# RC_Engine_Sound_ESP32.net
KiCad netlist of a schematic drawn in EAGLE
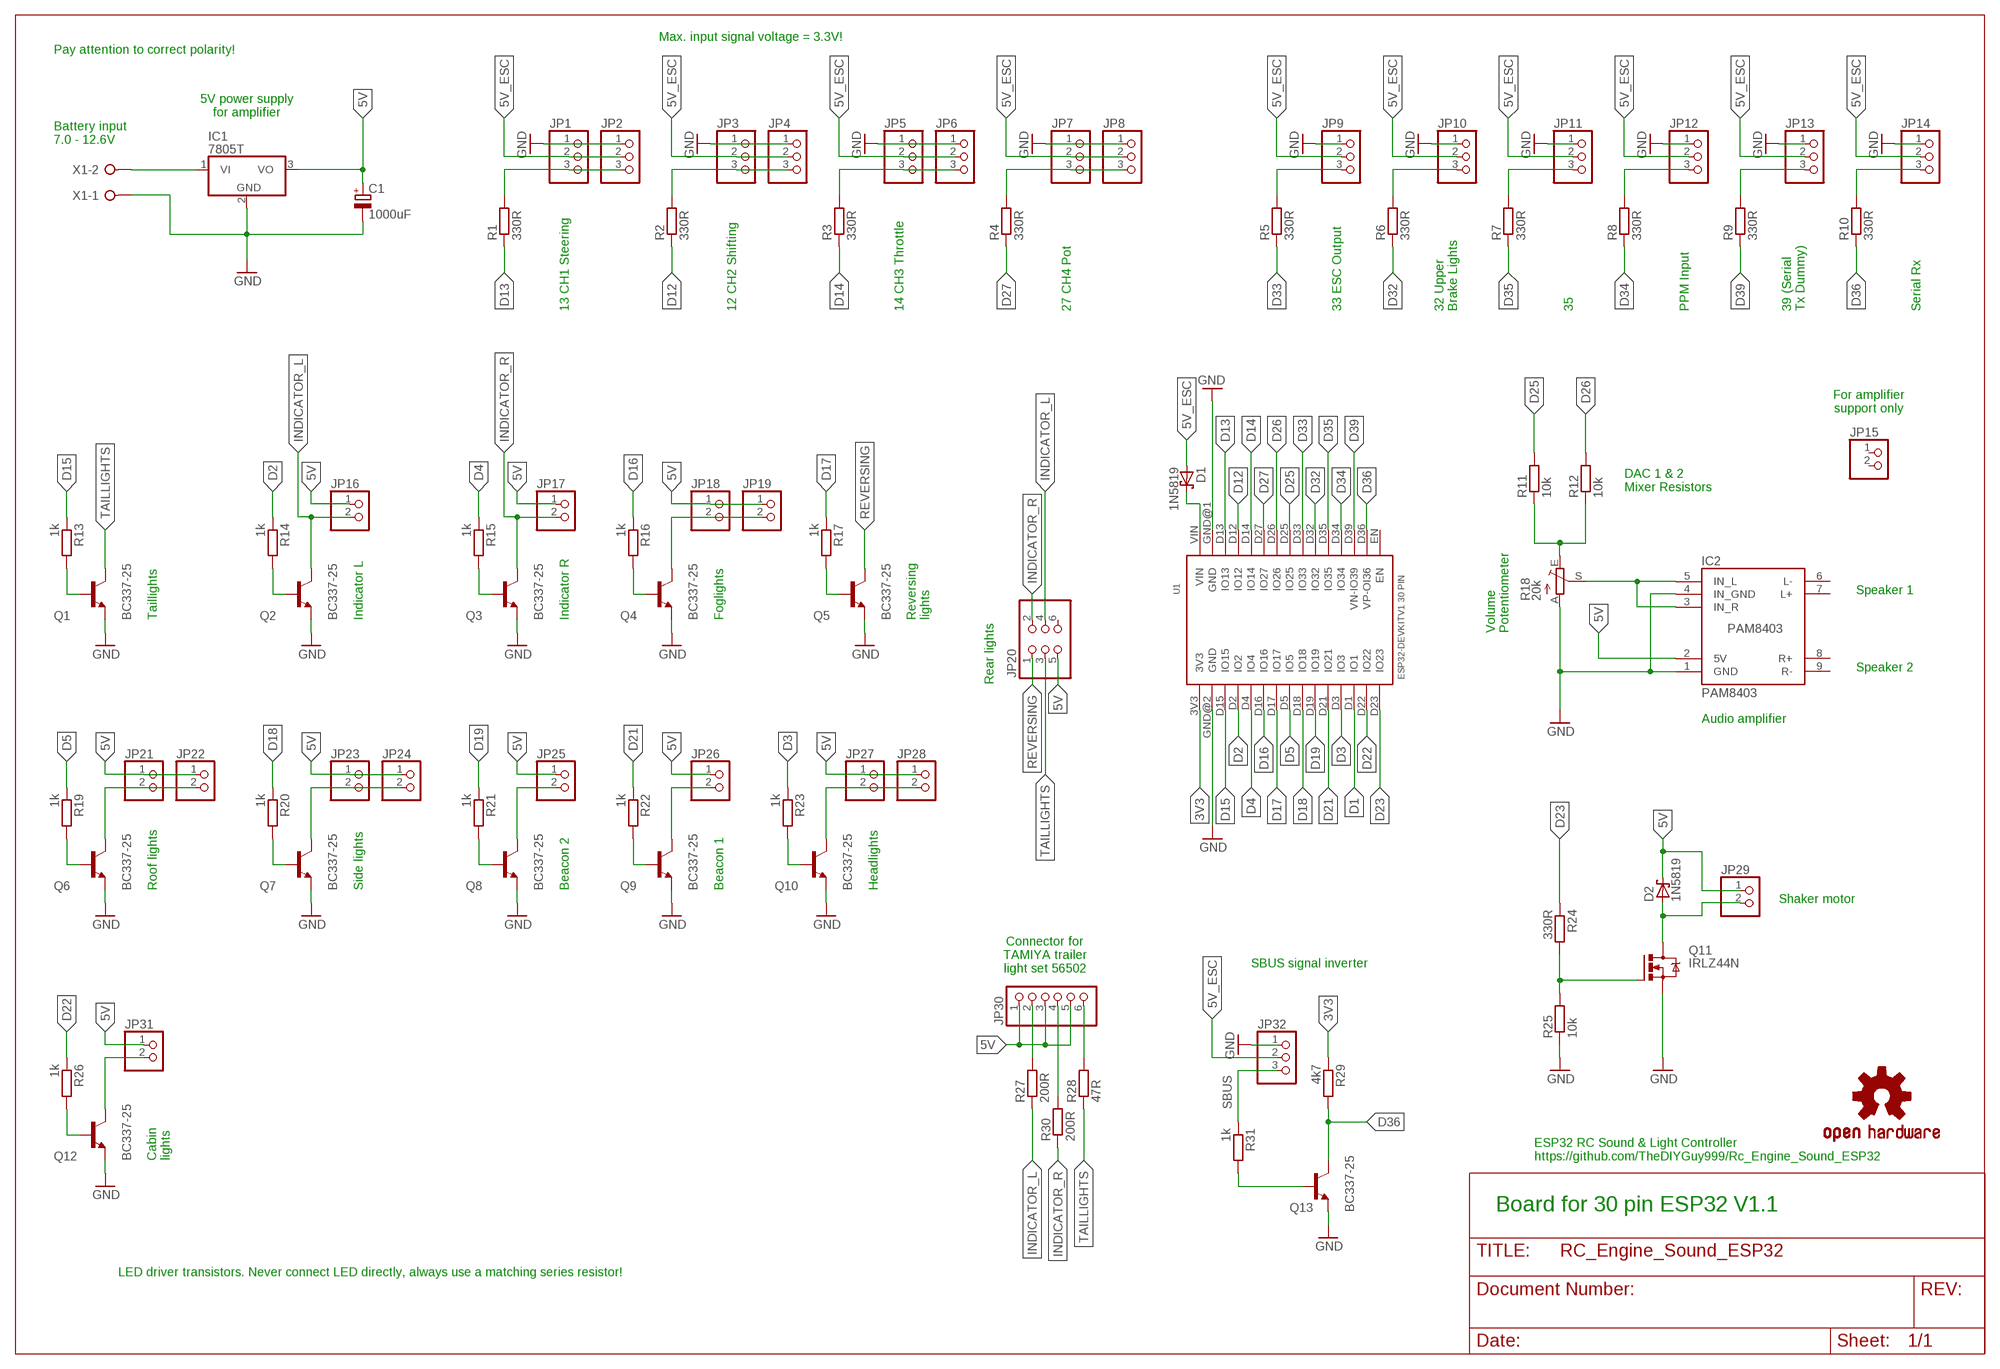
[diagram p0: schematic, sheet 1]

(export (version "E")
  (design (tool "Eeschema 10.0.6"))
  (components
    (comp (ref "C1")
      (value "1000uF")
      (footprint "eagle-import:E5-10,5")
      (libsource (lib "eagle-import") (part "CPOL-EUE5-10.5"))
    )
    (comp (ref "D1")
      (value "1N5819")
      (footprint "eagle-import:DO35-7")
      (libsource (lib "eagle-import") (part "SCHOTTKY-DIODEDO35-7"))
    )
    (comp (ref "D2")
      (value "1N5819")
      (footprint "eagle-import:DO35-7")
      (libsource (lib "eagle-import") (part "SCHOTTKY-DIODEDO35-7"))
    )
    (comp (ref "IC1")
      (value "7805T")
      (footprint "eagle-import:TO220H")
      (libsource (lib "eagle-import") (part "78T05"))
    )
    (comp (ref "IC2")
      (value "PAM8403")
      (footprint "eagle-import:PAM8403")
      (libsource (lib "eagle-import") (part "PAM8403"))
    )
    (comp (ref "JP1")
      (value "PINHD-1X3")
      (footprint "eagle-import:1X03")
      (libsource (lib "eagle-import") (part "PINHD-1X3"))
    )
    (comp (ref "JP2")
      (value "PINHD-1X3")
      (footprint "eagle-import:1X03")
      (libsource (lib "eagle-import") (part "PINHD-1X3"))
    )
    (comp (ref "JP3")
      (value "PINHD-1X3")
      (footprint "eagle-import:1X03")
      (libsource (lib "eagle-import") (part "PINHD-1X3"))
    )
    (comp (ref "JP4")
      (value "PINHD-1X3")
      (footprint "eagle-import:1X03")
      (libsource (lib "eagle-import") (part "PINHD-1X3"))
    )
    (comp (ref "JP5")
      (value "PINHD-1X3")
      (footprint "eagle-import:1X03")
      (libsource (lib "eagle-import") (part "PINHD-1X3"))
    )
    (comp (ref "JP6")
      (value "PINHD-1X3")
      (footprint "eagle-import:1X03")
      (libsource (lib "eagle-import") (part "PINHD-1X3"))
    )
    (comp (ref "JP7")
      (value "PINHD-1X3")
      (footprint "eagle-import:1X03")
      (libsource (lib "eagle-import") (part "PINHD-1X3"))
    )
    (comp (ref "JP8")
      (value "PINHD-1X3")
      (footprint "eagle-import:1X03")
      (libsource (lib "eagle-import") (part "PINHD-1X3"))
    )
    (comp (ref "JP9")
      (value "PINHD-1X3")
      (footprint "eagle-import:1X03")
      (libsource (lib "eagle-import") (part "PINHD-1X3"))
    )
    (comp (ref "JP10")
      (value "PINHD-1X3")
      (footprint "eagle-import:1X03")
      (libsource (lib "eagle-import") (part "PINHD-1X3"))
    )
    (comp (ref "JP11")
      (value "PINHD-1X3")
      (footprint "eagle-import:1X03")
      (libsource (lib "eagle-import") (part "PINHD-1X3"))
    )
    (comp (ref "JP12")
      (value "PINHD-1X3")
      (footprint "eagle-import:1X03")
      (libsource (lib "eagle-import") (part "PINHD-1X3"))
    )
    (comp (ref "JP13")
      (value "PINHD-1X3")
      (footprint "eagle-import:1X03")
      (libsource (lib "eagle-import") (part "PINHD-1X3"))
    )
    (comp (ref "JP14")
      (value "PINHD-1X3")
      (footprint "eagle-import:1X03")
      (libsource (lib "eagle-import") (part "PINHD-1X3"))
    )
    (comp (ref "JP15")
      (value "PINHD-1X2")
      (footprint "eagle-import:1X02")
      (libsource (lib "eagle-import") (part "PINHD-1X2"))
    )
    (comp (ref "JP16")
      (value "PINHD-1X2")
      (footprint "eagle-import:1X02")
      (libsource (lib "eagle-import") (part "PINHD-1X2"))
    )
    (comp (ref "JP17")
      (value "PINHD-1X2")
      (footprint "eagle-import:1X02")
      (libsource (lib "eagle-import") (part "PINHD-1X2"))
    )
    (comp (ref "JP18")
      (value "PINHD-1X2")
      (footprint "eagle-import:1X02")
      (libsource (lib "eagle-import") (part "PINHD-1X2"))
    )
    (comp (ref "JP19")
      (value "PINHD-1X2")
      (footprint "eagle-import:1X02")
      (libsource (lib "eagle-import") (part "PINHD-1X2"))
    )
    (comp (ref "JP20")
      (value "PINHD-2X3")
      (footprint "eagle-import:2X03")
      (libsource (lib "eagle-import") (part "PINHD-2X3"))
    )
    (comp (ref "JP21")
      (value "PINHD-1X2")
      (footprint "eagle-import:1X02")
      (libsource (lib "eagle-import") (part "PINHD-1X2"))
    )
    (comp (ref "JP22")
      (value "PINHD-1X2")
      (footprint "eagle-import:1X02")
      (libsource (lib "eagle-import") (part "PINHD-1X2"))
    )
    (comp (ref "JP23")
      (value "PINHD-1X2")
      (footprint "eagle-import:1X02")
      (libsource (lib "eagle-import") (part "PINHD-1X2"))
    )
    (comp (ref "JP24")
      (value "PINHD-1X2")
      (footprint "eagle-import:1X02")
      (libsource (lib "eagle-import") (part "PINHD-1X2"))
    )
    (comp (ref "JP25")
      (value "PINHD-1X2")
      (footprint "eagle-import:1X02")
      (libsource (lib "eagle-import") (part "PINHD-1X2"))
    )
    (comp (ref "JP26")
      (value "PINHD-1X2")
      (footprint "eagle-import:1X02")
      (libsource (lib "eagle-import") (part "PINHD-1X2"))
    )
    (comp (ref "JP27")
      (value "PINHD-1X2")
      (footprint "eagle-import:1X02")
      (libsource (lib "eagle-import") (part "PINHD-1X2"))
    )
    (comp (ref "JP28")
      (value "PINHD-1X2")
      (footprint "eagle-import:1X02")
      (libsource (lib "eagle-import") (part "PINHD-1X2"))
    )
    (comp (ref "JP29")
      (value "PINHD-1X2")
      (footprint "eagle-import:1X02")
      (libsource (lib "eagle-import") (part "PINHD-1X2"))
    )
    (comp (ref "JP30")
      (value "PINHD-1X6")
      (footprint "eagle-import:1X06")
      (libsource (lib "eagle-import") (part "PINHD-1X6"))
    )
    (comp (ref "JP31")
      (value "PINHD-1X2")
      (footprint "eagle-import:1X02")
      (libsource (lib "eagle-import") (part "PINHD-1X2"))
    )
    (comp (ref "JP32")
      (value "PINHD-1X3")
      (footprint "eagle-import:1X03")
      (libsource (lib "eagle-import") (part "PINHD-1X3"))
    )
    (comp (ref "LOGO1")
      (value "OSHW-LOGOM")
      (footprint "eagle-import:OSHW-LOGO-M")
      (libsource (lib "eagle-import") (part "OSHW-LOGOM"))
    )
    (comp (ref "Q1")
      (value "BC337-25")
      (footprint "eagle-import:TO92")
      (libsource (lib "eagle-import") (part "BC337-25"))
    )
    (comp (ref "Q2")
      (value "BC337-25")
      (footprint "eagle-import:TO92")
      (libsource (lib "eagle-import") (part "BC337-25"))
    )
    (comp (ref "Q3")
      (value "BC337-25")
      (footprint "eagle-import:TO92")
      (libsource (lib "eagle-import") (part "BC337-25"))
    )
    (comp (ref "Q4")
      (value "BC337-25")
      (footprint "eagle-import:TO92")
      (libsource (lib "eagle-import") (part "BC337-25"))
    )
    (comp (ref "Q5")
      (value "BC337-25")
      (footprint "eagle-import:TO92")
      (libsource (lib "eagle-import") (part "BC337-25"))
    )
    (comp (ref "Q6")
      (value "BC337-25")
      (footprint "eagle-import:TO92")
      (libsource (lib "eagle-import") (part "BC337-25"))
    )
    (comp (ref "Q7")
      (value "BC337-25")
      (footprint "eagle-import:TO92")
      (libsource (lib "eagle-import") (part "BC337-25"))
    )
    (comp (ref "Q8")
      (value "BC337-25")
      (footprint "eagle-import:TO92")
      (libsource (lib "eagle-import") (part "BC337-25"))
    )
    (comp (ref "Q9")
      (value "BC337-25")
      (footprint "eagle-import:TO92")
      (libsource (lib "eagle-import") (part "BC337-25"))
    )
    (comp (ref "Q10")
      (value "BC337-25")
      (footprint "eagle-import:TO92")
      (libsource (lib "eagle-import") (part "BC337-25"))
    )
    (comp (ref "Q11")
      (value "IRLZ44N")
      (footprint "eagle-import:TO220BV")
      (libsource (lib "eagle-import") (part "IRF540"))
    )
    (comp (ref "Q12")
      (value "BC337-25")
      (footprint "eagle-import:TO92")
      (libsource (lib "eagle-import") (part "BC337-25"))
    )
    (comp (ref "Q13")
      (value "BC337-25")
      (footprint "eagle-import:TO92")
      (libsource (lib "eagle-import") (part "BC337-25"))
    )
    (comp (ref "R1")
      (value "330R")
      (footprint "eagle-import:0207_2V")
      (libsource (lib "eagle-import") (part "R-EU_0207/2V"))
    )
    (comp (ref "R2")
      (value "330R")
      (footprint "eagle-import:0207_2V")
      (libsource (lib "eagle-import") (part "R-EU_0207/2V"))
    )
    (comp (ref "R3")
      (value "330R")
      (footprint "eagle-import:0207_2V")
      (libsource (lib "eagle-import") (part "R-EU_0207/2V"))
    )
    (comp (ref "R4")
      (value "330R")
      (footprint "eagle-import:0207_2V")
      (libsource (lib "eagle-import") (part "R-EU_0207/2V"))
    )
    (comp (ref "R5")
      (value "330R")
      (footprint "eagle-import:0207_2V")
      (libsource (lib "eagle-import") (part "R-EU_0207/2V"))
    )
    (comp (ref "R6")
      (value "330R")
      (footprint "eagle-import:0207_2V")
      (libsource (lib "eagle-import") (part "R-EU_0207/2V"))
    )
    (comp (ref "R7")
      (value "330R")
      (footprint "eagle-import:0207_2V")
      (libsource (lib "eagle-import") (part "R-EU_0207/2V"))
    )
    (comp (ref "R8")
      (value "330R")
      (footprint "eagle-import:0207_2V")
      (libsource (lib "eagle-import") (part "R-EU_0207/2V"))
    )
    (comp (ref "R9")
      (value "330R")
      (footprint "eagle-import:0207_2V")
      (libsource (lib "eagle-import") (part "R-EU_0207/2V"))
    )
    (comp (ref "R10")
      (value "330R")
      (footprint "eagle-import:0207_2V")
      (libsource (lib "eagle-import") (part "R-EU_0207/2V"))
    )
    (comp (ref "R11")
      (value "10k")
      (footprint "eagle-import:0207_10")
      (libsource (lib "eagle-import") (part "R-EU_0207/10"))
    )
    (comp (ref "R12")
      (value "10k")
      (footprint "eagle-import:0207_10")
      (libsource (lib "eagle-import") (part "R-EU_0207/10"))
    )
    (comp (ref "R13")
      (value "1k")
      (footprint "eagle-import:0207_2V")
      (libsource (lib "eagle-import") (part "R-EU_0207/2V"))
    )
    (comp (ref "R14")
      (value "1k")
      (footprint "eagle-import:0207_2V")
      (libsource (lib "eagle-import") (part "R-EU_0207/2V"))
    )
    (comp (ref "R15")
      (value "1k")
      (footprint "eagle-import:0207_2V")
      (libsource (lib "eagle-import") (part "R-EU_0207/2V"))
    )
    (comp (ref "R16")
      (value "1k")
      (footprint "eagle-import:0207_2V")
      (libsource (lib "eagle-import") (part "R-EU_0207/2V"))
    )
    (comp (ref "R17")
      (value "1k")
      (footprint "eagle-import:0207_2V")
      (libsource (lib "eagle-import") (part "R-EU_0207/2V"))
    )
    (comp (ref "R18")
      (value "20k")
      (footprint "eagle-import:S64W")
      (libsource (lib "eagle-import") (part "TRIM_EU-S64W"))
    )
    (comp (ref "R19")
      (value "1k")
      (footprint "eagle-import:0207_2V")
      (libsource (lib "eagle-import") (part "R-EU_0207/2V"))
    )
    (comp (ref "R20")
      (value "1k")
      (footprint "eagle-import:0207_2V")
      (libsource (lib "eagle-import") (part "R-EU_0207/2V"))
    )
    (comp (ref "R21")
      (value "1k")
      (footprint "eagle-import:0207_2V")
      (libsource (lib "eagle-import") (part "R-EU_0207/2V"))
    )
    (comp (ref "R22")
      (value "1k")
      (footprint "eagle-import:0207_2V")
      (libsource (lib "eagle-import") (part "R-EU_0207/2V"))
    )
    (comp (ref "R23")
      (value "1k")
      (footprint "eagle-import:0207_2V")
      (libsource (lib "eagle-import") (part "R-EU_0207/2V"))
    )
    (comp (ref "R24")
      (value "330R")
      (footprint "eagle-import:0207_2V")
      (libsource (lib "eagle-import") (part "R-EU_0207/2V"))
    )
    (comp (ref "R25")
      (value "10k")
      (footprint "eagle-import:0207_2V")
      (libsource (lib "eagle-import") (part "R-EU_0207/2V"))
    )
    (comp (ref "R26")
      (value "1k")
      (footprint "eagle-import:0207_2V")
      (libsource (lib "eagle-import") (part "R-EU_0207/2V"))
    )
    (comp (ref "R27")
      (value "200R")
      (footprint "eagle-import:0207_10")
      (libsource (lib "eagle-import") (part "R-EU_0207/10"))
    )
    (comp (ref "R28")
      (value "47R")
      (footprint "eagle-import:0207_10")
      (libsource (lib "eagle-import") (part "R-EU_0207/10"))
    )
    (comp (ref "R29")
      (value "4k7")
      (footprint "eagle-import:0207_2V")
      (libsource (lib "eagle-import") (part "R-EU_0207/2V"))
    )
    (comp (ref "R30")
      (value "200R")
      (footprint "eagle-import:0207_10")
      (libsource (lib "eagle-import") (part "R-EU_0207/10"))
    )
    (comp (ref "R31")
      (value "1k")
      (footprint "eagle-import:0207_2V")
      (libsource (lib "eagle-import") (part "R-EU_0207/2V"))
    )
    (comp (ref "U1")
      (value "ESP32DEVKITV1")
      (footprint "eagle-import:ESP32-DEVKITV1")
      (libsource (lib "eagle-import") (part "ESP32DEVKITV1"))
    )
    (comp (ref "X1")
      (value "W237-02P")
      (footprint "eagle-import:W237-132")
      (libsource (lib "eagle-import") (part "W237-02P"))
    )
  )
  (nets
    (net (code "1") (name "/SBUS") (class "Default")
      (node (ref "JP32") (pin "3") (pinfunction "3_3") (pintype "passive"))
      (node (ref "R31") (pin "1") (pinfunction "1_1") (pintype "passive"))
    )
    (net (code "2") (name "3V3") (class "Default")
      (node (ref "R29") (pin "1") (pinfunction "1_1") (pintype "passive"))
      (node (ref "U1") (pin "3V3") (pinfunction "3V3_3V3") (pintype "bidirectional"))
    )
    (net (code "3") (name "5V") (class "Default")
      (node (ref "C1") (pin "+") (pinfunction "+_+") (pintype "passive"))
      (node (ref "D2") (pin "C") (pinfunction "C_C") (pintype "passive"))
      (node (ref "IC1") (pin "3") (pinfunction "VO_3") (pintype "passive"))
      (node (ref "IC2") (pin "2") (pinfunction "5V_2") (pintype "input"))
      (node (ref "JP16") (pin "1") (pinfunction "1_1") (pintype "passive"))
      (node (ref "JP17") (pin "1") (pinfunction "1_1") (pintype "passive"))
      (node (ref "JP18") (pin "1") (pinfunction "1_1") (pintype "passive"))
      (node (ref "JP19") (pin "1") (pinfunction "1_1") (pintype "passive"))
      (node (ref "JP20") (pin "5") (pinfunction "5_5") (pintype "passive"))
      (node (ref "JP21") (pin "1") (pinfunction "1_1") (pintype "passive"))
      (node (ref "JP22") (pin "1") (pinfunction "1_1") (pintype "passive"))
      (node (ref "JP23") (pin "1") (pinfunction "1_1") (pintype "passive"))
      (node (ref "JP24") (pin "1") (pinfunction "1_1") (pintype "passive"))
      (node (ref "JP25") (pin "1") (pinfunction "1_1") (pintype "passive"))
      (node (ref "JP26") (pin "1") (pinfunction "1_1") (pintype "passive"))
      (node (ref "JP27") (pin "1") (pinfunction "1_1") (pintype "passive"))
      (node (ref "JP28") (pin "1") (pinfunction "1_1") (pintype "passive"))
      (node (ref "JP29") (pin "1") (pinfunction "1_1") (pintype "passive"))
      (node (ref "JP30") (pin "1") (pinfunction "1_1") (pintype "passive"))
      (node (ref "JP30") (pin "3") (pinfunction "3_3") (pintype "passive"))
      (node (ref "JP30") (pin "5") (pinfunction "5_5") (pintype "passive"))
      (node (ref "JP31") (pin "1") (pinfunction "1_1") (pintype "passive"))
    )
    (net (code "4") (name "5V_ESC") (class "Default")
      (node (ref "D1") (pin "A") (pinfunction "A_A") (pintype "passive"))
      (node (ref "JP1") (pin "2") (pinfunction "2_2") (pintype "passive"))
      (node (ref "JP10") (pin "2") (pinfunction "2_2") (pintype "passive"))
      (node (ref "JP11") (pin "2") (pinfunction "2_2") (pintype "passive"))
      (node (ref "JP12") (pin "2") (pinfunction "2_2") (pintype "passive"))
      (node (ref "JP13") (pin "2") (pinfunction "2_2") (pintype "passive"))
      (node (ref "JP14") (pin "2") (pinfunction "2_2") (pintype "passive"))
      (node (ref "JP2") (pin "2") (pinfunction "2_2") (pintype "passive"))
      (node (ref "JP3") (pin "2") (pinfunction "2_2") (pintype "passive"))
      (node (ref "JP32") (pin "2") (pinfunction "2_2") (pintype "passive"))
      (node (ref "JP4") (pin "2") (pinfunction "2_2") (pintype "passive"))
      (node (ref "JP5") (pin "2") (pinfunction "2_2") (pintype "passive"))
      (node (ref "JP6") (pin "2") (pinfunction "2_2") (pintype "passive"))
      (node (ref "JP7") (pin "2") (pinfunction "2_2") (pintype "passive"))
      (node (ref "JP8") (pin "2") (pinfunction "2_2") (pintype "passive"))
      (node (ref "JP9") (pin "2") (pinfunction "2_2") (pintype "passive"))
    )
    (net (code "5") (name "D1") (class "Default")
      (node (ref "U1") (pin "D1") (pinfunction "IO1_D1") (pintype "bidirectional"))
    )
    (net (code "6") (name "D2") (class "Default")
      (node (ref "R14") (pin "1") (pinfunction "1_1") (pintype "passive"))
      (node (ref "U1") (pin "D2") (pinfunction "IO2_D2") (pintype "bidirectional"))
    )
    (net (code "7") (name "D3") (class "Default")
      (node (ref "R23") (pin "1") (pinfunction "1_1") (pintype "passive"))
      (node (ref "U1") (pin "D3") (pinfunction "IO3_D3") (pintype "bidirectional"))
    )
    (net (code "8") (name "D4") (class "Default")
      (node (ref "R15") (pin "1") (pinfunction "1_1") (pintype "passive"))
      (node (ref "U1") (pin "D4") (pinfunction "IO4_D4") (pintype "bidirectional"))
    )
    (net (code "9") (name "D5") (class "Default")
      (node (ref "R19") (pin "1") (pinfunction "1_1") (pintype "passive"))
      (node (ref "U1") (pin "D5") (pinfunction "IO5_D5") (pintype "bidirectional"))
    )
    (net (code "10") (name "D12") (class "Default")
      (node (ref "R2") (pin "1") (pinfunction "1_1") (pintype "passive"))
      (node (ref "U1") (pin "D12") (pinfunction "IO12_D12") (pintype "bidirectional"))
    )
    (net (code "11") (name "D13") (class "Default")
      (node (ref "R1") (pin "1") (pinfunction "1_1") (pintype "passive"))
      (node (ref "U1") (pin "D13") (pinfunction "IO13_D13") (pintype "bidirectional"))
    )
    (net (code "12") (name "D14") (class "Default")
      (node (ref "R3") (pin "1") (pinfunction "1_1") (pintype "passive"))
      (node (ref "U1") (pin "D14") (pinfunction "IO14_D14") (pintype "bidirectional"))
    )
    (net (code "13") (name "D15") (class "Default")
      (node (ref "R13") (pin "1") (pinfunction "1_1") (pintype "passive"))
      (node (ref "U1") (pin "D15") (pinfunction "IO15_D15") (pintype "bidirectional"))
    )
    (net (code "14") (name "D16") (class "Default")
      (node (ref "R16") (pin "1") (pinfunction "1_1") (pintype "passive"))
      (node (ref "U1") (pin "D16") (pinfunction "IO16_D16") (pintype "bidirectional"))
    )
    (net (code "15") (name "D17") (class "Default")
      (node (ref "R17") (pin "1") (pinfunction "1_1") (pintype "passive"))
      (node (ref "U1") (pin "D17") (pinfunction "IO17_D17") (pintype "bidirectional"))
    )
    (net (code "16") (name "D18") (class "Default")
      (node (ref "R20") (pin "1") (pinfunction "1_1") (pintype "passive"))
      (node (ref "U1") (pin "D18") (pinfunction "IO18_D18") (pintype "bidirectional"))
    )
    (net (code "17") (name "D19") (class "Default")
      (node (ref "R21") (pin "1") (pinfunction "1_1") (pintype "passive"))
      (node (ref "U1") (pin "D19") (pinfunction "IO19_D19") (pintype "bidirectional"))
    )
    (net (code "18") (name "D21") (class "Default")
      (node (ref "R22") (pin "1") (pinfunction "1_1") (pintype "passive"))
      (node (ref "U1") (pin "D21") (pinfunction "IO21_D21") (pintype "bidirectional"))
    )
    (net (code "19") (name "D22") (class "Default")
      (node (ref "R26") (pin "1") (pinfunction "1_1") (pintype "passive"))
      (node (ref "U1") (pin "D22") (pinfunction "IO22_D22") (pintype "bidirectional"))
    )
    (net (code "20") (name "D23") (class "Default")
      (node (ref "R24") (pin "1") (pinfunction "1_1") (pintype "passive"))
      (node (ref "U1") (pin "D23") (pinfunction "IO23_D23") (pintype "bidirectional"))
    )
    (net (code "21") (name "D25") (class "Default")
      (node (ref "R11") (pin "2") (pinfunction "2_2") (pintype "passive"))
      (node (ref "U1") (pin "D25") (pinfunction "IO25_D25") (pintype "bidirectional"))
    )
    (net (code "22") (name "D26") (class "Default")
      (node (ref "R12") (pin "2") (pinfunction "2_2") (pintype "passive"))
      (node (ref "U1") (pin "D26") (pinfunction "IO26_D26") (pintype "bidirectional"))
    )
    (net (code "23") (name "D27") (class "Default")
      (node (ref "R4") (pin "1") (pinfunction "1_1") (pintype "passive"))
      (node (ref "U1") (pin "D27") (pinfunction "IO27_D27") (pintype "bidirectional"))
    )
    (net (code "24") (name "D32") (class "Default")
      (node (ref "R6") (pin "1") (pinfunction "1_1") (pintype "passive"))
      (node (ref "U1") (pin "D32") (pinfunction "IO32_D32") (pintype "bidirectional"))
    )
    (net (code "25") (name "D33") (class "Default")
      (node (ref "R5") (pin "1") (pinfunction "1_1") (pintype "passive"))
      (node (ref "U1") (pin "D33") (pinfunction "IO33_D33") (pintype "bidirectional"))
    )
    (net (code "26") (name "D34") (class "Default")
      (node (ref "R8") (pin "1") (pinfunction "1_1") (pintype "passive"))
      (node (ref "U1") (pin "D34") (pinfunction "IO34_D34") (pintype "bidirectional"))
    )
    (net (code "27") (name "D35") (class "Default")
      (node (ref "R7") (pin "1") (pinfunction "1_1") (pintype "passive"))
      (node (ref "U1") (pin "D35") (pinfunction "IO35_D35") (pintype "bidirectional"))
    )
    (net (code "28") (name "D36") (class "Default")
      (node (ref "Q13") (pin "3") (pinfunction "C_3") (pintype "passive"))
      (node (ref "R10") (pin "1") (pinfunction "1_1") (pintype "passive"))
      (node (ref "R29") (pin "2") (pinfunction "2_2") (pintype "passive"))
      (node (ref "U1") (pin "D36") (pinfunction "VP-OI36_D36") (pintype "bidirectional"))
    )
    (net (code "29") (name "D39") (class "Default")
      (node (ref "R9") (pin "1") (pinfunction "1_1") (pintype "passive"))
      (node (ref "U1") (pin "D39") (pinfunction "VN-IO39_D39") (pintype "bidirectional"))
    )
    (net (code "30") (name "GND") (class "Default")
      (node (ref "C1") (pin "-") (pinfunction "-_-") (pintype "passive"))
      (node (ref "IC1") (pin "2") (pinfunction "GND_2") (pintype "passive"))
      (node (ref "IC2") (pin "1") (pinfunction "GND_1") (pintype "input"))
      (node (ref "IC2") (pin "4") (pinfunction "IN_GND_4") (pintype "input"))
      (node (ref "JP1") (pin "1") (pinfunction "1_1") (pintype "passive"))
      (node (ref "JP10") (pin "1") (pinfunction "1_1") (pintype "passive"))
      (node (ref "JP11") (pin "1") (pinfunction "1_1") (pintype "passive"))
      (node (ref "JP12") (pin "1") (pinfunction "1_1") (pintype "passive"))
      (node (ref "JP13") (pin "1") (pinfunction "1_1") (pintype "passive"))
      (node (ref "JP14") (pin "1") (pinfunction "1_1") (pintype "passive"))
      (node (ref "JP2") (pin "1") (pinfunction "1_1") (pintype "passive"))
      (node (ref "JP3") (pin "1") (pinfunction "1_1") (pintype "passive"))
      (node (ref "JP32") (pin "1") (pinfunction "1_1") (pintype "passive"))
      (node (ref "JP4") (pin "1") (pinfunction "1_1") (pintype "passive"))
      (node (ref "JP5") (pin "1") (pinfunction "1_1") (pintype "passive"))
      (node (ref "JP6") (pin "1") (pinfunction "1_1") (pintype "passive"))
      (node (ref "JP7") (pin "1") (pinfunction "1_1") (pintype "passive"))
      (node (ref "JP8") (pin "1") (pinfunction "1_1") (pintype "passive"))
      (node (ref "JP9") (pin "1") (pinfunction "1_1") (pintype "passive"))
      (node (ref "Q1") (pin "1") (pinfunction "E_1") (pintype "passive"))
      (node (ref "Q10") (pin "1") (pinfunction "E_1") (pintype "passive"))
      (node (ref "Q11") (pin "S") (pinfunction "S_S") (pintype "passive"))
      (node (ref "Q12") (pin "1") (pinfunction "E_1") (pintype "passive"))
      (node (ref "Q13") (pin "1") (pinfunction "E_1") (pintype "passive"))
      (node (ref "Q2") (pin "1") (pinfunction "E_1") (pintype "passive"))
      (node (ref "Q3") (pin "1") (pinfunction "E_1") (pintype "passive"))
      (node (ref "Q4") (pin "1") (pinfunction "E_1") (pintype "passive"))
      (node (ref "Q5") (pin "1") (pinfunction "E_1") (pintype "passive"))
      (node (ref "Q6") (pin "1") (pinfunction "E_1") (pintype "passive"))
      (node (ref "Q7") (pin "1") (pinfunction "E_1") (pintype "passive"))
      (node (ref "Q8") (pin "1") (pinfunction "E_1") (pintype "passive"))
      (node (ref "Q9") (pin "1") (pinfunction "E_1") (pintype "passive"))
      (node (ref "R18") (pin "A") (pinfunction "A_A") (pintype "passive"))
      (node (ref "R25") (pin "1") (pinfunction "1_1") (pintype "passive"))
      (node (ref "U1") (pin "GND@1") (pinfunction "GND_GND@1") (pintype "bidirectional"))
      (node (ref "U1") (pin "GND@2") (pinfunction "GND_GND@2") (pintype "bidirectional"))
      (node (ref "X1") (pin "1") (pinfunction "KL_1") (pintype "passive"))
    )
    (net (code "31") (name "INDICATOR_L") (class "Default")
      (node (ref "JP16") (pin "2") (pinfunction "2_2") (pintype "passive"))
      (node (ref "JP20") (pin "4") (pinfunction "4_4") (pintype "passive"))
      (node (ref "Q2") (pin "3") (pinfunction "C_3") (pintype "passive"))
      (node (ref "R27") (pin "1") (pinfunction "1_1") (pintype "passive"))
    )
    (net (code "32") (name "INDICATOR_R") (class "Default")
      (node (ref "JP17") (pin "2") (pinfunction "2_2") (pintype "passive"))
      (node (ref "JP20") (pin "2") (pinfunction "2_2") (pintype "passive"))
      (node (ref "Q3") (pin "3") (pinfunction "C_3") (pintype "passive"))
      (node (ref "R30") (pin "1") (pinfunction "1_1") (pintype "passive"))
    )
    (net (code "33") (name "Net-(D1-PadC)") (class "Default")
      (node (ref "D1") (pin "C") (pinfunction "C_C") (pintype "passive"))
      (node (ref "U1") (pin "VIN") (pinfunction "VIN_VIN") (pintype "bidirectional"))
    )
    (net (code "34") (name "Net-(D2-PadA)") (class "Default")
      (node (ref "D2") (pin "A") (pinfunction "A_A") (pintype "passive"))
      (node (ref "JP29") (pin "2") (pinfunction "2_2") (pintype "passive"))
      (node (ref "Q11") (pin "D") (pinfunction "D_D") (pintype "passive"))
    )
    (net (code "35") (name "Net-(IC1-VI)") (class "Default")
      (node (ref "IC1") (pin "1") (pinfunction "VI_1") (pintype "input"))
      (node (ref "X1") (pin "2") (pinfunction "KL_2") (pintype "passive"))
    )
    (net (code "36") (name "Net-(IC2-IN_L)") (class "Default")
      (node (ref "IC2") (pin "3") (pinfunction "IN_R_3") (pintype "input"))
      (node (ref "IC2") (pin "5") (pinfunction "IN_L_5") (pintype "input"))
      (node (ref "R18") (pin "S") (pinfunction "S_S") (pintype "passive"))
    )
    (net (code "37") (name "Net-(JP1-Pad3)") (class "Default")
      (node (ref "JP1") (pin "3") (pinfunction "3_3") (pintype "passive"))
      (node (ref "JP2") (pin "3") (pinfunction "3_3") (pintype "passive"))
      (node (ref "R1") (pin "2") (pinfunction "2_2") (pintype "passive"))
    )
    (net (code "38") (name "Net-(JP3-Pad3)") (class "Default")
      (node (ref "JP3") (pin "3") (pinfunction "3_3") (pintype "passive"))
      (node (ref "JP4") (pin "3") (pinfunction "3_3") (pintype "passive"))
      (node (ref "R2") (pin "2") (pinfunction "2_2") (pintype "passive"))
    )
    (net (code "39") (name "Net-(JP5-Pad3)") (class "Default")
      (node (ref "JP5") (pin "3") (pinfunction "3_3") (pintype "passive"))
      (node (ref "JP6") (pin "3") (pinfunction "3_3") (pintype "passive"))
      (node (ref "R3") (pin "2") (pinfunction "2_2") (pintype "passive"))
    )
    (net (code "40") (name "Net-(JP7-Pad3)") (class "Default")
      (node (ref "JP7") (pin "3") (pinfunction "3_3") (pintype "passive"))
      (node (ref "JP8") (pin "3") (pinfunction "3_3") (pintype "passive"))
      (node (ref "R4") (pin "2") (pinfunction "2_2") (pintype "passive"))
    )
    (net (code "41") (name "Net-(JP9-Pad3)") (class "Default")
      (node (ref "JP9") (pin "3") (pinfunction "3_3") (pintype "passive"))
      (node (ref "R5") (pin "2") (pinfunction "2_2") (pintype "passive"))
    )
    (net (code "42") (name "Net-(JP10-Pad3)") (class "Default")
      (node (ref "JP10") (pin "3") (pinfunction "3_3") (pintype "passive"))
      (node (ref "R6") (pin "2") (pinfunction "2_2") (pintype "passive"))
    )
    (net (code "43") (name "Net-(JP11-Pad3)") (class "Default")
      (node (ref "JP11") (pin "3") (pinfunction "3_3") (pintype "passive"))
      (node (ref "R7") (pin "2") (pinfunction "2_2") (pintype "passive"))
    )
    (net (code "44") (name "Net-(JP12-Pad3)") (class "Default")
      (node (ref "JP12") (pin "3") (pinfunction "3_3") (pintype "passive"))
      (node (ref "R8") (pin "2") (pinfunction "2_2") (pintype "passive"))
    )
    (net (code "45") (name "Net-(JP13-Pad3)") (class "Default")
      (node (ref "JP13") (pin "3") (pinfunction "3_3") (pintype "passive"))
      (node (ref "R9") (pin "2") (pinfunction "2_2") (pintype "passive"))
    )
    (net (code "46") (name "Net-(JP14-Pad3)") (class "Default")
      (node (ref "JP14") (pin "3") (pinfunction "3_3") (pintype "passive"))
      (node (ref "R10") (pin "2") (pinfunction "2_2") (pintype "passive"))
    )
    (net (code "47") (name "Net-(JP30-Pad2)") (class "Default")
      (node (ref "JP30") (pin "2") (pinfunction "2_2") (pintype "passive"))
      (node (ref "R27") (pin "2") (pinfunction "2_2") (pintype "passive"))
    )
    (net (code "48") (name "Net-(JP30-Pad4)") (class "Default")
      (node (ref "JP30") (pin "4") (pinfunction "4_4") (pintype "passive"))
      (node (ref "R30") (pin "2") (pinfunction "2_2") (pintype "passive"))
    )
    (net (code "49") (name "Net-(JP30-Pad6)") (class "Default")
      (node (ref "JP30") (pin "6") (pinfunction "6_6") (pintype "passive"))
      (node (ref "R28") (pin "2") (pinfunction "2_2") (pintype "passive"))
    )
    (net (code "50") (name "Net-(Q1-B)") (class "Default")
      (node (ref "Q1") (pin "2") (pinfunction "B_2") (pintype "passive"))
      (node (ref "R13") (pin "2") (pinfunction "2_2") (pintype "passive"))
    )
    (net (code "51") (name "Net-(Q2-B)") (class "Default")
      (node (ref "Q2") (pin "2") (pinfunction "B_2") (pintype "passive"))
      (node (ref "R14") (pin "2") (pinfunction "2_2") (pintype "passive"))
    )
    (net (code "52") (name "Net-(Q3-B)") (class "Default")
      (node (ref "Q3") (pin "2") (pinfunction "B_2") (pintype "passive"))
      (node (ref "R15") (pin "2") (pinfunction "2_2") (pintype "passive"))
    )
    (net (code "53") (name "Net-(Q4-B)") (class "Default")
      (node (ref "Q4") (pin "2") (pinfunction "B_2") (pintype "passive"))
      (node (ref "R16") (pin "2") (pinfunction "2_2") (pintype "passive"))
    )
    (net (code "54") (name "Net-(Q4-C)") (class "Default")
      (node (ref "JP18") (pin "2") (pinfunction "2_2") (pintype "passive"))
      (node (ref "JP19") (pin "2") (pinfunction "2_2") (pintype "passive"))
      (node (ref "Q4") (pin "3") (pinfunction "C_3") (pintype "passive"))
    )
    (net (code "55") (name "Net-(Q5-B)") (class "Default")
      (node (ref "Q5") (pin "2") (pinfunction "B_2") (pintype "passive"))
      (node (ref "R17") (pin "2") (pinfunction "2_2") (pintype "passive"))
    )
    (net (code "56") (name "Net-(Q6-B)") (class "Default")
      (node (ref "Q6") (pin "2") (pinfunction "B_2") (pintype "passive"))
      (node (ref "R19") (pin "2") (pinfunction "2_2") (pintype "passive"))
    )
    (net (code "57") (name "Net-(Q6-C)") (class "Default")
      (node (ref "JP21") (pin "2") (pinfunction "2_2") (pintype "passive"))
      (node (ref "JP22") (pin "2") (pinfunction "2_2") (pintype "passive"))
      (node (ref "Q6") (pin "3") (pinfunction "C_3") (pintype "passive"))
    )
    (net (code "58") (name "Net-(Q7-B)") (class "Default")
      (node (ref "Q7") (pin "2") (pinfunction "B_2") (pintype "passive"))
      (node (ref "R20") (pin "2") (pinfunction "2_2") (pintype "passive"))
    )
    (net (code "59") (name "Net-(Q7-C)") (class "Default")
      (node (ref "JP23") (pin "2") (pinfunction "2_2") (pintype "passive"))
      (node (ref "JP24") (pin "2") (pinfunction "2_2") (pintype "passive"))
      (node (ref "Q7") (pin "3") (pinfunction "C_3") (pintype "passive"))
    )
    (net (code "60") (name "Net-(Q8-B)") (class "Default")
      (node (ref "Q8") (pin "2") (pinfunction "B_2") (pintype "passive"))
      (node (ref "R21") (pin "2") (pinfunction "2_2") (pintype "passive"))
    )
    (net (code "61") (name "Net-(Q8-C)") (class "Default")
      (node (ref "JP25") (pin "2") (pinfunction "2_2") (pintype "passive"))
      (node (ref "Q8") (pin "3") (pinfunction "C_3") (pintype "passive"))
    )
    (net (code "62") (name "Net-(Q9-B)") (class "Default")
      (node (ref "Q9") (pin "2") (pinfunction "B_2") (pintype "passive"))
      (node (ref "R22") (pin "2") (pinfunction "2_2") (pintype "passive"))
    )
    (net (code "63") (name "Net-(Q9-C)") (class "Default")
      (node (ref "JP26") (pin "2") (pinfunction "2_2") (pintype "passive"))
      (node (ref "Q9") (pin "3") (pinfunction "C_3") (pintype "passive"))
    )
    (net (code "64") (name "Net-(Q10-B)") (class "Default")
      (node (ref "Q10") (pin "2") (pinfunction "B_2") (pintype "passive"))
      (node (ref "R23") (pin "2") (pinfunction "2_2") (pintype "passive"))
    )
    (net (code "65") (name "Net-(Q10-C)") (class "Default")
      (node (ref "JP27") (pin "2") (pinfunction "2_2") (pintype "passive"))
      (node (ref "JP28") (pin "2") (pinfunction "2_2") (pintype "passive"))
      (node (ref "Q10") (pin "3") (pinfunction "C_3") (pintype "passive"))
    )
    (net (code "66") (name "Net-(Q11-PadG)") (class "Default")
      (node (ref "Q11") (pin "G") (pinfunction "G_G") (pintype "passive"))
      (node (ref "R24") (pin "2") (pinfunction "2_2") (pintype "passive"))
      (node (ref "R25") (pin "2") (pinfunction "2_2") (pintype "passive"))
    )
    (net (code "67") (name "Net-(Q12-B)") (class "Default")
      (node (ref "Q12") (pin "2") (pinfunction "B_2") (pintype "passive"))
      (node (ref "R26") (pin "2") (pinfunction "2_2") (pintype "passive"))
    )
    (net (code "68") (name "Net-(Q12-C)") (class "Default")
      (node (ref "JP31") (pin "2") (pinfunction "2_2") (pintype "passive"))
      (node (ref "Q12") (pin "3") (pinfunction "C_3") (pintype "passive"))
    )
    (net (code "69") (name "Net-(Q13-B)") (class "Default")
      (node (ref "Q13") (pin "2") (pinfunction "B_2") (pintype "passive"))
      (node (ref "R31") (pin "2") (pinfunction "2_2") (pintype "passive"))
    )
    (net (code "70") (name "Net-(R11-Pad1)") (class "Default")
      (node (ref "R11") (pin "1") (pinfunction "1_1") (pintype "passive"))
      (node (ref "R12") (pin "1") (pinfunction "1_1") (pintype "passive"))
      (node (ref "R18") (pin "E") (pinfunction "E_E") (pintype "passive"))
    )
    (net (code "71") (name "REVERSING") (class "Default")
      (node (ref "JP20") (pin "1") (pinfunction "1_1") (pintype "passive"))
      (node (ref "Q5") (pin "3") (pinfunction "C_3") (pintype "passive"))
    )
    (net (code "72") (name "TAILLIGHTS") (class "Default")
      (node (ref "JP20") (pin "3") (pinfunction "3_3") (pintype "passive"))
      (node (ref "Q1") (pin "3") (pinfunction "C_3") (pintype "passive"))
      (node (ref "R28") (pin "1") (pinfunction "1_1") (pintype "passive"))
    )
    (net (code "73") (name "unconnected-(IC2-L+-Pad7)") (class "Default")
      (node (ref "IC2") (pin "7") (pinfunction "L+_7") (pintype "output"))
    )
    (net (code "74") (name "unconnected-(IC2-L--Pad6)") (class "Default")
      (node (ref "IC2") (pin "6") (pinfunction "L-_6") (pintype "output"))
    )
    (net (code "75") (name "unconnected-(IC2-R+-Pad8)") (class "Default")
      (node (ref "IC2") (pin "8") (pinfunction "R+_8") (pintype "output"))
    )
    (net (code "76") (name "unconnected-(IC2-R--Pad9)") (class "Default")
      (node (ref "IC2") (pin "9") (pinfunction "R-_9") (pintype "output"))
    )
    (net (code "77") (name "unconnected-(JP15-Pad1)") (class "Default")
      (node (ref "JP15") (pin "1") (pinfunction "1_1") (pintype "passive"))
    )
    (net (code "78") (name "unconnected-(JP15-Pad2)") (class "Default")
      (node (ref "JP15") (pin "2") (pinfunction "2_2") (pintype "passive"))
    )
    (net (code "79") (name "unconnected-(JP20-Pad6)") (class "Default")
      (node (ref "JP20") (pin "6") (pinfunction "6_6") (pintype "passive"))
    )
    (net (code "80") (name "unconnected-(U1-PadEN)") (class "Default")
      (node (ref "U1") (pin "EN") (pinfunction "EN_EN") (pintype "bidirectional"))
    )
  )
)
